# FM_RECEIVER.net
KiCad netlist of a schematic drawn in EAGLE
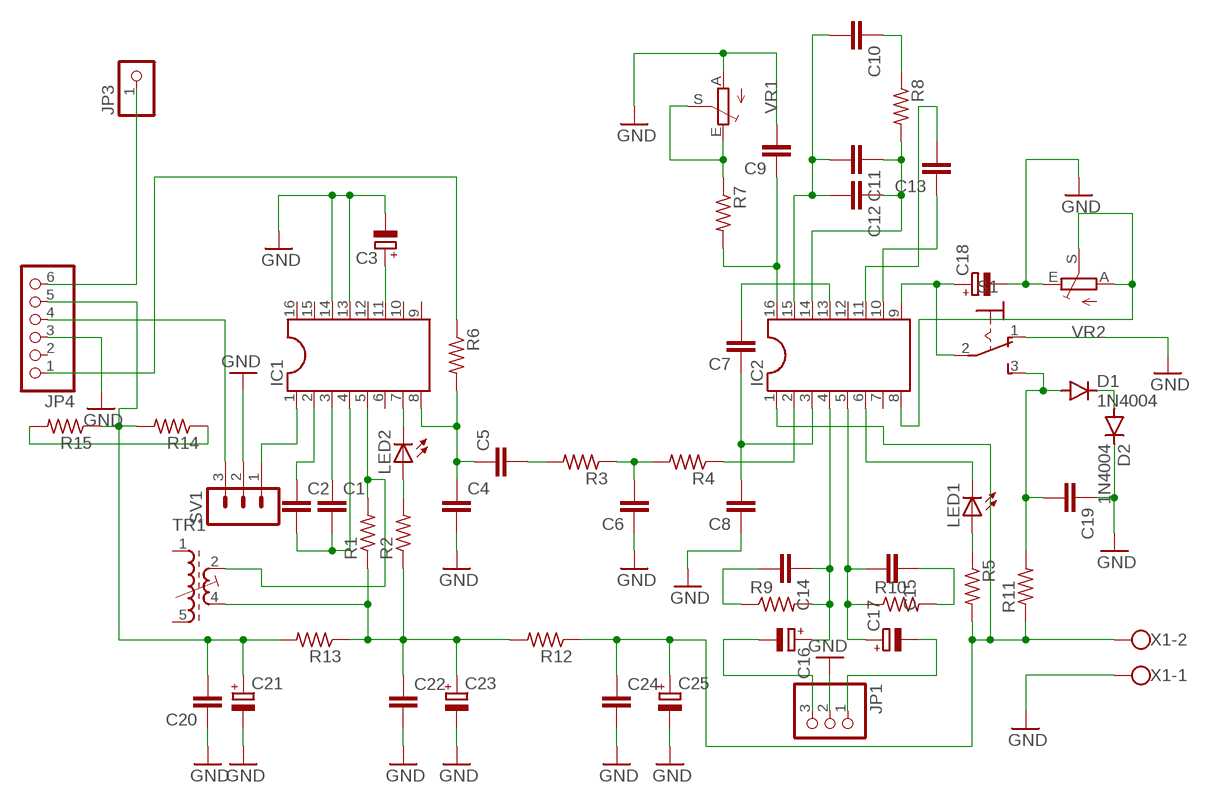
[diagram p0: schematic, sheet 1]

(export (version "E")
  (design (tool "Eeschema 10.0.6"))
  (components
    (comp (ref "C1")
      (value "C-EU050-025X075")
      (footprint "eagle-import:C050-025X075")
      (libsource (lib "eagle-import") (part "C-EU050-025X075"))
    )
    (comp (ref "C2")
      (value "C-EU050-025X075")
      (footprint "eagle-import:C050-025X075")
      (libsource (lib "eagle-import") (part "C-EU050-025X075"))
    )
    (comp (ref "C3")
      (value "CPOL-EUE2,5-6E")
      (footprint "eagle-import:E2,5-6E")
      (libsource (lib "eagle-import") (part "CPOL-EUE2,5-6E"))
    )
    (comp (ref "C4")
      (value "C-EU050-025X075")
      (footprint "eagle-import:C050-025X075")
      (libsource (lib "eagle-import") (part "C-EU050-025X075"))
    )
    (comp (ref "C5")
      (value "C-EU050-025X075")
      (footprint "eagle-import:C050-025X075")
      (libsource (lib "eagle-import") (part "C-EU050-025X075"))
    )
    (comp (ref "C6")
      (value "C-EU050-025X075")
      (footprint "eagle-import:C050-025X075")
      (libsource (lib "eagle-import") (part "C-EU050-025X075"))
    )
    (comp (ref "C7")
      (value "C-EU050-025X075")
      (footprint "eagle-import:C050-025X075")
      (libsource (lib "eagle-import") (part "C-EU050-025X075"))
    )
    (comp (ref "C8")
      (value "C-EU050-025X075")
      (footprint "eagle-import:C050-025X075")
      (libsource (lib "eagle-import") (part "C-EU050-025X075"))
    )
    (comp (ref "C9")
      (value "C-EU050-025X075")
      (footprint "eagle-import:C050-025X075")
      (libsource (lib "eagle-import") (part "C-EU050-025X075"))
    )
    (comp (ref "C10")
      (value "C-EU050-025X075")
      (footprint "eagle-import:C050-025X075")
      (libsource (lib "eagle-import") (part "C-EU050-025X075"))
    )
    (comp (ref "C11")
      (value "C-EU050-025X075")
      (footprint "eagle-import:C050-025X075")
      (libsource (lib "eagle-import") (part "C-EU050-025X075"))
    )
    (comp (ref "C12")
      (value "C-EU050-025X075")
      (footprint "eagle-import:C050-025X075")
      (libsource (lib "eagle-import") (part "C-EU050-025X075"))
    )
    (comp (ref "C13")
      (value "C-EU050-025X075")
      (footprint "eagle-import:C050-025X075")
      (libsource (lib "eagle-import") (part "C-EU050-025X075"))
    )
    (comp (ref "C14")
      (value "C-EU050-025X075")
      (footprint "eagle-import:C050-025X075")
      (libsource (lib "eagle-import") (part "C-EU050-025X075"))
    )
    (comp (ref "C15")
      (value "C-EU050-025X075")
      (footprint "eagle-import:C050-025X075")
      (libsource (lib "eagle-import") (part "C-EU050-025X075"))
    )
    (comp (ref "C16")
      (value "CPOL-EUE2,5-6E")
      (footprint "eagle-import:E2,5-6E")
      (libsource (lib "eagle-import") (part "CPOL-EUE2,5-6E"))
    )
    (comp (ref "C17")
      (value "CPOL-EUE2,5-6E")
      (footprint "eagle-import:E2,5-6E")
      (libsource (lib "eagle-import") (part "CPOL-EUE2,5-6E"))
    )
    (comp (ref "C18")
      (value "CPOL-EUE2,5-6E")
      (footprint "eagle-import:E2,5-6E")
      (libsource (lib "eagle-import") (part "CPOL-EUE2,5-6E"))
    )
    (comp (ref "C19")
      (value "C-EU050-025X075")
      (footprint "eagle-import:C050-025X075")
      (libsource (lib "eagle-import") (part "C-EU050-025X075"))
    )
    (comp (ref "C20")
      (value "C-EU050-025X075")
      (footprint "eagle-import:C050-025X075")
      (libsource (lib "eagle-import") (part "C-EU050-025X075"))
    )
    (comp (ref "C21")
      (value "CPOL-EUE2,5-6E")
      (footprint "eagle-import:E2,5-6E")
      (libsource (lib "eagle-import") (part "CPOL-EUE2,5-6E"))
    )
    (comp (ref "C22")
      (value "C-EU050-025X075")
      (footprint "eagle-import:C050-025X075")
      (libsource (lib "eagle-import") (part "C-EU050-025X075"))
    )
    (comp (ref "C23")
      (value "CPOL-EUE2,5-6E")
      (footprint "eagle-import:E2,5-6E")
      (libsource (lib "eagle-import") (part "CPOL-EUE2,5-6E"))
    )
    (comp (ref "C24")
      (value "C-EU050-025X075")
      (footprint "eagle-import:C050-025X075")
      (libsource (lib "eagle-import") (part "C-EU050-025X075"))
    )
    (comp (ref "C25")
      (value "CPOL-EUE2,5-6E")
      (footprint "eagle-import:E2,5-6E")
      (libsource (lib "eagle-import") (part "CPOL-EUE2,5-6E"))
    )
    (comp (ref "D1")
      (value "1N4004")
      (footprint "eagle-import:DO41-10")
      (libsource (lib "eagle-import") (part "1N4004"))
    )
    (comp (ref "D2")
      (value "1N4004")
      (footprint "eagle-import:DO41-10")
      (libsource (lib "eagle-import") (part "1N4004"))
    )
    (comp (ref "IC1")
      (value "DIL16")
      (footprint "eagle-import:DIL16")
      (libsource (lib "eagle-import") (part "DIL16"))
    )
    (comp (ref "IC2")
      (value "DIL16")
      (footprint "eagle-import:DIL16")
      (libsource (lib "eagle-import") (part "DIL16"))
    )
    (comp (ref "JP1")
      (value "PINHD-1X3")
      (footprint "eagle-import:1X03")
      (libsource (lib "eagle-import") (part "PINHD-1X3"))
    )
    (comp (ref "JP3")
      (value "PINHD-1X1")
      (footprint "eagle-import:1X01")
      (libsource (lib "eagle-import") (part "PINHD-1X1"))
    )
    (comp (ref "JP4")
      (value "PINHD-1X6")
      (footprint "eagle-import:1X06")
      (libsource (lib "eagle-import") (part "PINHD-1X6"))
    )
    (comp (ref "LED1")
      (value "LED3MM")
      (footprint "eagle-import:LED3MM")
      (libsource (lib "eagle-import") (part "LED3MM"))
    )
    (comp (ref "LED2")
      (value "LED3MM")
      (footprint "eagle-import:LED3MM")
      (libsource (lib "eagle-import") (part "LED3MM"))
    )
    (comp (ref "R1")
      (value "R-US_0207/10")
      (footprint "eagle-import:0207_10")
      (libsource (lib "eagle-import") (part "R-US_0207/10"))
    )
    (comp (ref "R2")
      (value "R-US_0207/10")
      (footprint "eagle-import:0207_10")
      (libsource (lib "eagle-import") (part "R-US_0207/10"))
    )
    (comp (ref "R3")
      (value "R-US_0207/10")
      (footprint "eagle-import:0207_10")
      (libsource (lib "eagle-import") (part "R-US_0207/10"))
    )
    (comp (ref "R4")
      (value "R-US_0207/10")
      (footprint "eagle-import:0207_10")
      (libsource (lib "eagle-import") (part "R-US_0207/10"))
    )
    (comp (ref "R5")
      (value "R-US_0207/10")
      (footprint "eagle-import:0207_10")
      (libsource (lib "eagle-import") (part "R-US_0207/10"))
    )
    (comp (ref "R6")
      (value "R-US_0207/10")
      (footprint "eagle-import:0207_10")
      (libsource (lib "eagle-import") (part "R-US_0207/10"))
    )
    (comp (ref "R7")
      (value "R-US_0207/10")
      (footprint "eagle-import:0207_10")
      (libsource (lib "eagle-import") (part "R-US_0207/10"))
    )
    (comp (ref "R8")
      (value "R-US_0207/10")
      (footprint "eagle-import:0207_10")
      (libsource (lib "eagle-import") (part "R-US_0207/10"))
    )
    (comp (ref "R9")
      (value "R-US_0207/10")
      (footprint "eagle-import:0207_10")
      (libsource (lib "eagle-import") (part "R-US_0207/10"))
    )
    (comp (ref "R10")
      (value "R-US_0207/10")
      (footprint "eagle-import:0207_10")
      (libsource (lib "eagle-import") (part "R-US_0207/10"))
    )
    (comp (ref "R11")
      (value "R-US_0207/10")
      (footprint "eagle-import:0207_10")
      (libsource (lib "eagle-import") (part "R-US_0207/10"))
    )
    (comp (ref "R12")
      (value "R-US_0207/10")
      (footprint "eagle-import:0207_10")
      (libsource (lib "eagle-import") (part "R-US_0207/10"))
    )
    (comp (ref "R13")
      (value "R-US_0207/10")
      (footprint "eagle-import:0207_10")
      (libsource (lib "eagle-import") (part "R-US_0207/10"))
    )
    (comp (ref "R14")
      (value "R-US_0207/10")
      (footprint "eagle-import:0207_10")
      (libsource (lib "eagle-import") (part "R-US_0207/10"))
    )
    (comp (ref "R15")
      (value "R-US_0207/10")
      (footprint "eagle-import:0207_10")
      (libsource (lib "eagle-import") (part "R-US_0207/10"))
    )
    (comp (ref "S1")
      (value "320-916")
      (footprint "eagle-import:320-916")
      (libsource (lib "eagle-import") (part "320-916"))
    )
    (comp (ref "SV1")
      (value "MA03-1")
      (footprint "eagle-import:MA03-1")
      (libsource (lib "eagle-import") (part "MA03-1"))
    )
    (comp (ref "TR1")
      (value "71-4-1542")
      (footprint "eagle-import:71-5")
      (libsource (lib "eagle-import") (part "71-4-1542"))
    )
    (comp (ref "VR1")
      (value "TRIM_EU-CA6V")
      (footprint "eagle-import:CA6V")
      (libsource (lib "eagle-import") (part "TRIM_EU-CA6V"))
    )
    (comp (ref "VR2")
      (value "TRIM_EU-CA6V")
      (footprint "eagle-import:CA6V")
      (libsource (lib "eagle-import") (part "TRIM_EU-CA6V"))
    )
    (comp (ref "X1")
      (value "W237-102")
      (footprint "eagle-import:W237-102")
      (fields (field (name "MPN") "237-102"))
      (libsource (lib "eagle-import") (part "W237-102"))
    )
  )
  (nets
    (net (code "1") (name "GND") (class "Default")
      (node (ref "C18") (pin "-") (pinfunction "-_-") (pintype "passive"))
      (node (ref "C19") (pin "1") (pinfunction "1_1") (pintype "passive"))
      (node (ref "C20") (pin "1") (pinfunction "1_1") (pintype "passive"))
      (node (ref "C21") (pin "-") (pinfunction "-_-") (pintype "passive"))
      (node (ref "C22") (pin "2") (pinfunction "2_2") (pintype "passive"))
      (node (ref "C23") (pin "-") (pinfunction "-_-") (pintype "passive"))
      (node (ref "C24") (pin "2") (pinfunction "2_2") (pintype "passive"))
      (node (ref "C25") (pin "-") (pinfunction "-_-") (pintype "passive"))
      (node (ref "C3") (pin "-") (pinfunction "-_-") (pintype "passive"))
      (node (ref "C4") (pin "2") (pinfunction "2_2") (pintype "passive"))
      (node (ref "C6") (pin "1") (pinfunction "1_1") (pintype "passive"))
      (node (ref "C8") (pin "1") (pinfunction "1_1") (pintype "passive"))
      (node (ref "C9") (pin "2") (pinfunction "2_2") (pintype "passive"))
      (node (ref "D2") (pin "C") (pinfunction "C_C") (pintype "passive"))
      (node (ref "IC1") (pin "13") (pinfunction "13_13") (pintype "passive"))
      (node (ref "IC1") (pin "14") (pinfunction "14_14") (pintype "passive"))
      (node (ref "JP1") (pin "2") (pinfunction "2_2") (pintype "passive"))
      (node (ref "JP4") (pin "3") (pinfunction "3_3") (pintype "passive"))
      (node (ref "S1") (pin "1") (pinfunction "O_1") (pintype "passive"))
      (node (ref "SV1") (pin "2") (pinfunction "2_2") (pintype "passive"))
      (node (ref "VR1") (pin "A") (pinfunction "A_A") (pintype "passive"))
      (node (ref "VR2") (pin "E") (pinfunction "E_E") (pintype "passive"))
      (node (ref "X1") (pin "1") (pinfunction "KL_1") (pintype "passive"))
    )
    (net (code "2") (name "Net-(C1-Pad1)") (class "Default")
      (node (ref "C1") (pin "1") (pinfunction "1_1") (pintype "passive"))
      (node (ref "IC1") (pin "3") (pinfunction "3_3") (pintype "passive"))
    )
    (net (code "3") (name "Net-(C1-Pad2)") (class "Default")
      (node (ref "C1") (pin "2") (pinfunction "2_2") (pintype "passive"))
      (node (ref "C2") (pin "2") (pinfunction "2_2") (pintype "passive"))
      (node (ref "IC1") (pin "4") (pinfunction "4_4") (pintype "passive"))
    )
    (net (code "4") (name "Net-(C2-Pad1)") (class "Default")
      (node (ref "C2") (pin "1") (pinfunction "1_1") (pintype "passive"))
      (node (ref "IC1") (pin "2") (pinfunction "2_2") (pintype "passive"))
    )
    (net (code "5") (name "Net-(C3-Pad+)") (class "Default")
      (node (ref "C3") (pin "+") (pinfunction "+_+") (pintype "passive"))
      (node (ref "IC1") (pin "11") (pinfunction "11_11") (pintype "passive"))
    )
    (net (code "6") (name "Net-(C4-Pad1)") (class "Default")
      (node (ref "C4") (pin "1") (pinfunction "1_1") (pintype "passive"))
      (node (ref "C5") (pin "1") (pinfunction "1_1") (pintype "passive"))
      (node (ref "IC1") (pin "8") (pinfunction "8_8") (pintype "passive"))
      (node (ref "R6") (pin "2") (pinfunction "2_2") (pintype "passive"))
    )
    (net (code "7") (name "Net-(C5-Pad2)") (class "Default")
      (node (ref "C5") (pin "2") (pinfunction "2_2") (pintype "passive"))
      (node (ref "R3") (pin "2") (pinfunction "2_2") (pintype "passive"))
    )
    (net (code "8") (name "Net-(C6-Pad2)") (class "Default")
      (node (ref "C6") (pin "2") (pinfunction "2_2") (pintype "passive"))
      (node (ref "R3") (pin "1") (pinfunction "1_1") (pintype "passive"))
      (node (ref "R4") (pin "2") (pinfunction "2_2") (pintype "passive"))
    )
    (net (code "9") (name "Net-(C7-Pad1)") (class "Default")
      (node (ref "C7") (pin "1") (pinfunction "1_1") (pintype "passive"))
      (node (ref "C8") (pin "2") (pinfunction "2_2") (pintype "passive"))
      (node (ref "IC2") (pin "3") (pinfunction "3_3") (pintype "passive"))
    )
    (net (code "10") (name "Net-(C7-Pad2)") (class "Default")
      (node (ref "C7") (pin "2") (pinfunction "2_2") (pintype "passive"))
      (node (ref "IC2") (pin "13") (pinfunction "13_13") (pintype "passive"))
    )
    (net (code "11") (name "Net-(C9-Pad1)") (class "Default")
      (node (ref "C9") (pin "1") (pinfunction "1_1") (pintype "passive"))
      (node (ref "IC2") (pin "16") (pinfunction "16_16") (pintype "passive"))
      (node (ref "R7") (pin "2") (pinfunction "2_2") (pintype "passive"))
    )
    (net (code "12") (name "Net-(C10-Pad1)") (class "Default")
      (node (ref "C10") (pin "1") (pinfunction "1_1") (pintype "passive"))
      (node (ref "R8") (pin "1") (pinfunction "1_1") (pintype "passive"))
    )
    (net (code "13") (name "Net-(C10-Pad2)") (class "Default")
      (node (ref "C10") (pin "2") (pinfunction "2_2") (pintype "passive"))
      (node (ref "C11") (pin "2") (pinfunction "2_2") (pintype "passive"))
      (node (ref "C12") (pin "2") (pinfunction "2_2") (pintype "passive"))
      (node (ref "IC2") (pin "15") (pinfunction "15_15") (pintype "passive"))
    )
    (net (code "14") (name "Net-(C11-Pad1)") (class "Default")
      (node (ref "C11") (pin "1") (pinfunction "1_1") (pintype "passive"))
      (node (ref "C12") (pin "1") (pinfunction "1_1") (pintype "passive"))
      (node (ref "IC2") (pin "14") (pinfunction "14_14") (pintype "passive"))
      (node (ref "R8") (pin "2") (pinfunction "2_2") (pintype "passive"))
    )
    (net (code "15") (name "Net-(C13-Pad1)") (class "Default")
      (node (ref "C13") (pin "1") (pinfunction "1_1") (pintype "passive"))
      (node (ref "IC2") (pin "10") (pinfunction "10_10") (pintype "passive"))
    )
    (net (code "16") (name "Net-(C13-Pad2)") (class "Default")
      (node (ref "C13") (pin "2") (pinfunction "2_2") (pintype "passive"))
      (node (ref "IC2") (pin "11") (pinfunction "11_11") (pintype "passive"))
    )
    (net (code "17") (name "Net-(C14-Pad1)") (class "Default")
      (node (ref "C14") (pin "1") (pinfunction "1_1") (pintype "passive"))
      (node (ref "C16") (pin "+") (pinfunction "+_+") (pintype "passive"))
      (node (ref "IC2") (pin "4") (pinfunction "4_4") (pintype "passive"))
      (node (ref "R9") (pin "2") (pinfunction "2_2") (pintype "passive"))
    )
    (net (code "18") (name "Net-(C14-Pad2)") (class "Default")
      (node (ref "C14") (pin "2") (pinfunction "2_2") (pintype "passive"))
      (node (ref "R9") (pin "1") (pinfunction "1_1") (pintype "passive"))
    )
    (net (code "19") (name "Net-(C15-Pad1)") (class "Default")
      (node (ref "C15") (pin "1") (pinfunction "1_1") (pintype "passive"))
      (node (ref "R10") (pin "2") (pinfunction "2_2") (pintype "passive"))
    )
    (net (code "20") (name "Net-(C15-Pad2)") (class "Default")
      (node (ref "C15") (pin "2") (pinfunction "2_2") (pintype "passive"))
      (node (ref "C17") (pin "+") (pinfunction "+_+") (pintype "passive"))
      (node (ref "IC2") (pin "5") (pinfunction "5_5") (pintype "passive"))
      (node (ref "R10") (pin "1") (pinfunction "1_1") (pintype "passive"))
    )
    (net (code "21") (name "Net-(C16-Pad-)") (class "Default")
      (node (ref "C16") (pin "-") (pinfunction "-_-") (pintype "passive"))
      (node (ref "JP1") (pin "3") (pinfunction "3_3") (pintype "passive"))
    )
    (net (code "22") (name "Net-(C17-Pad-)") (class "Default")
      (node (ref "C17") (pin "-") (pinfunction "-_-") (pintype "passive"))
      (node (ref "JP1") (pin "1") (pinfunction "1_1") (pintype "passive"))
    )
    (net (code "23") (name "Net-(C20-Pad2)") (class "Default")
      (node (ref "C20") (pin "2") (pinfunction "2_2") (pintype "passive"))
      (node (ref "C21") (pin "+") (pinfunction "+_+") (pintype "passive"))
      (node (ref "JP4") (pin "5") (pinfunction "5_5") (pintype "passive"))
      (node (ref "R13") (pin "2") (pinfunction "2_2") (pintype "passive"))
      (node (ref "R14") (pin "2") (pinfunction "2_2") (pintype "passive"))
      (node (ref "R15") (pin "1") (pinfunction "1_1") (pintype "passive"))
    )
    (net (code "24") (name "Net-(D1-PadC)") (class "Default")
      (node (ref "D1") (pin "C") (pinfunction "C_C") (pintype "passive"))
      (node (ref "D2") (pin "A") (pinfunction "A_A") (pintype "passive"))
    )
    (net (code "25") (name "Net-(IC1-Pad1)") (class "Default")
      (node (ref "IC1") (pin "1") (pinfunction "1_1") (pintype "passive"))
      (node (ref "SV1") (pin "1") (pinfunction "1_1") (pintype "passive"))
    )
    (net (code "26") (name "Net-(IC2-Pad2)") (class "Default")
      (node (ref "IC2") (pin "2") (pinfunction "2_2") (pintype "passive"))
      (node (ref "R4") (pin "1") (pinfunction "1_1") (pintype "passive"))
    )
    (net (code "27") (name "Net-(IC2-Pad8)") (class "Default")
      (node (ref "IC2") (pin "8") (pinfunction "8_8") (pintype "passive"))
      (node (ref "VR2") (pin "A") (pinfunction "A_A") (pintype "passive"))
      (node (ref "VR2") (pin "S") (pinfunction "S_S") (pintype "passive"))
    )
    (net (code "28") (name "Net-(JP3-Pad1)") (class "Default")
      (node (ref "JP3") (pin "1") (pinfunction "1_1") (pintype "passive"))
      (node (ref "JP4") (pin "6") (pinfunction "6_6") (pintype "passive"))
    )
    (net (code "29") (name "Net-(JP4-Pad1)") (class "Default")
      (node (ref "JP4") (pin "1") (pinfunction "1_1") (pintype "passive"))
      (node (ref "R6") (pin "1") (pinfunction "1_1") (pintype "passive"))
    )
    (net (code "30") (name "Net-(JP4-Pad4)") (class "Default")
      (node (ref "JP4") (pin "4") (pinfunction "4_4") (pintype "passive"))
      (node (ref "SV1") (pin "3") (pinfunction "3_3") (pintype "passive"))
    )
    (net (code "31") (name "Net-(LED1-C)") (class "Default")
      (node (ref "IC2") (pin "6") (pinfunction "6_6") (pintype "passive"))
      (node (ref "LED1") (pin "K") (pinfunction "C_K") (pintype "passive"))
    )
    (net (code "32") (name "Net-(LED1-PadA)") (class "Default")
      (node (ref "LED1") (pin "A") (pinfunction "A_A") (pintype "passive"))
      (node (ref "R5") (pin "1") (pinfunction "1_1") (pintype "passive"))
    )
    (net (code "33") (name "Net-(LED2-C)") (class "Default")
      (node (ref "IC1") (pin "7") (pinfunction "7_7") (pintype "passive"))
      (node (ref "LED2") (pin "K") (pinfunction "C_K") (pintype "passive"))
    )
    (net (code "34") (name "Net-(LED2-PadA)") (class "Default")
      (node (ref "LED2") (pin "A") (pinfunction "A_A") (pintype "passive"))
      (node (ref "R2") (pin "2") (pinfunction "2_2") (pintype "passive"))
    )
    (net (code "35") (name "Net-(R7-Pad1)") (class "Default")
      (node (ref "R7") (pin "1") (pinfunction "1_1") (pintype "passive"))
      (node (ref "VR1") (pin "E") (pinfunction "E_E") (pintype "passive"))
      (node (ref "VR1") (pin "S") (pinfunction "S_S") (pintype "passive"))
    )
    (net (code "36") (name "Net-(R14-Pad1)") (class "Default")
      (node (ref "R14") (pin "1") (pinfunction "1_1") (pintype "passive"))
      (node (ref "R15") (pin "2") (pinfunction "2_2") (pintype "passive"))
    )
    (net (code "37") (name "Net-(S1-P)") (class "Default")
      (node (ref "C18") (pin "+") (pinfunction "+_+") (pintype "passive"))
      (node (ref "IC2") (pin "9") (pinfunction "9_9") (pintype "passive"))
      (node (ref "S1") (pin "2") (pinfunction "P_2") (pintype "passive"))
    )
    (net (code "38") (name "Net-(S1-S)") (class "Default")
      (node (ref "C19") (pin "2") (pinfunction "2_2") (pintype "passive"))
      (node (ref "D1") (pin "A") (pinfunction "A_A") (pintype "passive"))
      (node (ref "R11") (pin "2") (pinfunction "2_2") (pintype "passive"))
      (node (ref "S1") (pin "3") (pinfunction "S_3") (pintype "passive"))
    )
    (net (code "39") (name "Net-(TR1A-A2)") (class "Default")
      (node (ref "IC1") (pin "5") (pinfunction "5_5") (pintype "passive"))
      (node (ref "R1") (pin "2") (pinfunction "2_2") (pintype "passive"))
      (node (ref "TR1") (pin "2") (pinfunction "A2_2") (pintype "passive"))
    )
    (net (code "40") (name "Net-(TR1A-E2)") (class "Default")
      (node (ref "C22") (pin "1") (pinfunction "1_1") (pintype "passive"))
      (node (ref "C23") (pin "+") (pinfunction "+_+") (pintype "passive"))
      (node (ref "R1") (pin "1") (pinfunction "1_1") (pintype "passive"))
      (node (ref "R12") (pin "2") (pinfunction "2_2") (pintype "passive"))
      (node (ref "R13") (pin "1") (pinfunction "1_1") (pintype "passive"))
      (node (ref "R2") (pin "1") (pinfunction "1_1") (pintype "passive"))
      (node (ref "TR1") (pin "4") (pinfunction "E2_4") (pintype "passive"))
    )
    (net (code "41") (name "Net-(X1B-KL)") (class "Default")
      (node (ref "C24") (pin "1") (pinfunction "1_1") (pintype "passive"))
      (node (ref "C25") (pin "+") (pinfunction "+_+") (pintype "passive"))
      (node (ref "IC2") (pin "1") (pinfunction "1_1") (pintype "passive"))
      (node (ref "R11") (pin "1") (pinfunction "1_1") (pintype "passive"))
      (node (ref "R12") (pin "1") (pinfunction "1_1") (pintype "passive"))
      (node (ref "R5") (pin "2") (pinfunction "2_2") (pintype "passive"))
      (node (ref "X1") (pin "2") (pinfunction "KL_2") (pintype "passive"))
    )
    (net (code "42") (name "unconnected-(IC1-Pad6)") (class "Default")
      (node (ref "IC1") (pin "6") (pinfunction "6_6") (pintype "passive"))
    )
    (net (code "43") (name "unconnected-(IC1-Pad9)") (class "Default")
      (node (ref "IC1") (pin "9") (pinfunction "9_9") (pintype "passive"))
    )
    (net (code "44") (name "unconnected-(IC1-Pad10)") (class "Default")
      (node (ref "IC1") (pin "10") (pinfunction "10_10") (pintype "passive"))
    )
    (net (code "45") (name "unconnected-(IC1-Pad12)") (class "Default")
      (node (ref "IC1") (pin "12") (pinfunction "12_12") (pintype "passive"))
    )
    (net (code "46") (name "unconnected-(IC1-Pad15)") (class "Default")
      (node (ref "IC1") (pin "15") (pinfunction "15_15") (pintype "passive"))
    )
    (net (code "47") (name "unconnected-(IC1-Pad16)") (class "Default")
      (node (ref "IC1") (pin "16") (pinfunction "16_16") (pintype "passive"))
    )
    (net (code "48") (name "unconnected-(IC2-Pad7)") (class "Default")
      (node (ref "IC2") (pin "7") (pinfunction "7_7") (pintype "passive"))
    )
    (net (code "49") (name "unconnected-(IC2-Pad12)") (class "Default")
      (node (ref "IC2") (pin "12") (pinfunction "12_12") (pintype "passive"))
    )
    (net (code "50") (name "unconnected-(JP4-Pad2)") (class "Default")
      (node (ref "JP4") (pin "2") (pinfunction "2_2") (pintype "passive"))
    )
    (net (code "51") (name "unconnected-(TR1A-A1-Pad1)") (class "Default")
      (node (ref "TR1") (pin "1") (pinfunction "A1_1") (pintype "passive"))
    )
    (net (code "52") (name "unconnected-(TR1A-E1-Pad5)") (class "Default")
      (node (ref "TR1") (pin "5") (pinfunction "E1_5") (pintype "passive"))
    )
  )
)
